# Main.net
KiCad netlist of a schematic drawn in Altium Designer
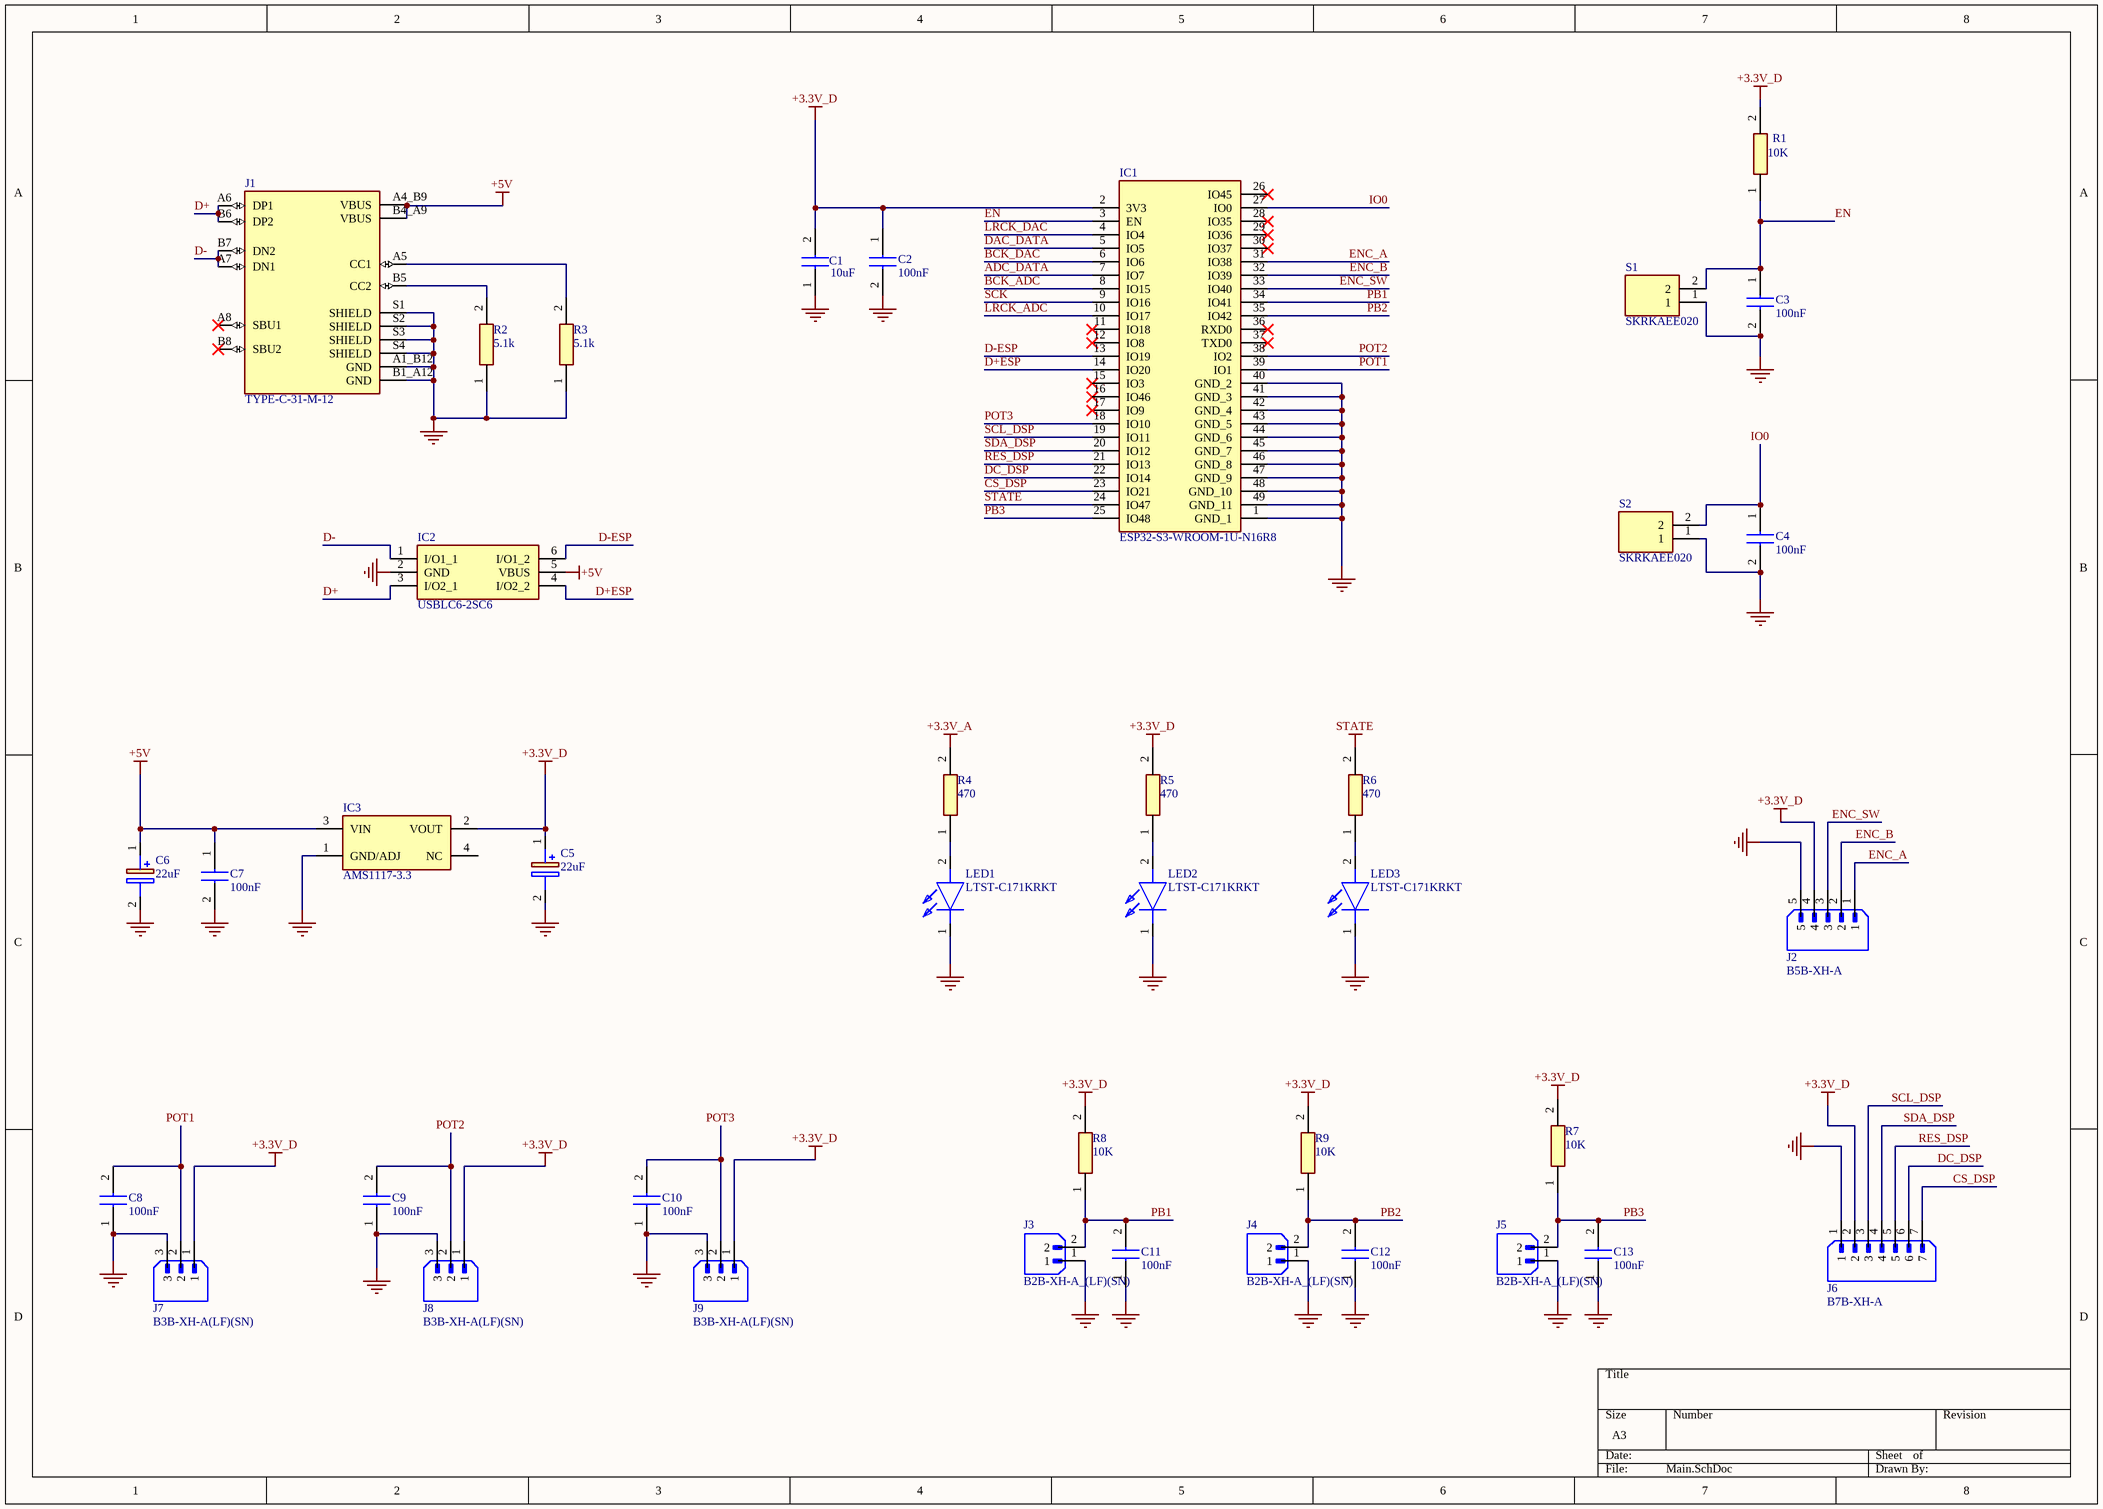
[diagram p0: Main.SchDoc]

(export (version "E")
  (design (tool "Eeschema 10.0.6"))
  (components
    (comp (ref "C1")
      (value "10uF")
      (footprint "SamacSys:CAPC3216X180N")
      (description "Capacitor")
      (fields
        (field (name "MANUFACTURER_PART_NUMBER") "CL31A106KAHNNNE")
        (field (name "MOUSER PART NUMBER") "187-CL31A106KAHNNNE")
      )
      (libsource (lib "SamacSys") (part "CL31A106KAHNNNE"))
    )
    (comp (ref "C2")
      (value "100nF")
      (footprint "SamacSys:CAPC1608X90N")
      (description "Capacitor")
      (fields
        (field (name "MANUFACTURER_PART_NUMBER") "CL10B104KC8NNNC")
        (field (name "MOUSER PART NUMBER") "187-CL10B104KC8NNNC")
      )
      (libsource (lib "SamacSys") (part "CL10B104KC8NNNC"))
    )
    (comp (ref "C3")
      (value "100nF")
      (footprint "SamacSys:CAPC1608X90N")
      (description "Capacitor")
      (fields
        (field (name "MANUFACTURER_PART_NUMBER") "CL10B104KC8NNNC")
        (field (name "MOUSER PART NUMBER") "187-CL10B104KC8NNNC")
      )
      (libsource (lib "SamacSys") (part "CL10B104KC8NNNC"))
    )
    (comp (ref "C4")
      (value "100nF")
      (footprint "SamacSys:CAPC1608X90N")
      (description "Capacitor")
      (fields
        (field (name "MANUFACTURER_PART_NUMBER") "CL10B104KC8NNNC")
        (field (name "MOUSER PART NUMBER") "187-CL10B104KC8NNNC")
      )
      (libsource (lib "SamacSys") (part "CL10B104KC8NNNC"))
    )
    (comp (ref "C5")
      (value "22uF")
      (footprint "SamacSys:CAPAE430X590N")
      (description "Capacitor Polarised")
      (fields (field (name "MANUFACTURER_PART_NUMBER") "RVT1C220M0405"))
      (libsource (lib "*") (part "RVT1C220M0405"))
    )
    (comp (ref "C6")
      (value "22uF")
      (footprint "SamacSys:CAPAE430X590N")
      (description "Capacitor Polarised")
      (fields (field (name "MANUFACTURER_PART_NUMBER") "RVT1C220M0405"))
      (libsource (lib "*") (part "RVT1C220M0405"))
    )
    (comp (ref "C7")
      (value "100nF")
      (footprint "SamacSys:CAPC1608X90N")
      (description "Capacitor")
      (fields
        (field (name "MANUFACTURER_PART_NUMBER") "CL10B104KC8NNNC")
        (field (name "MOUSER PART NUMBER") "187-CL10B104KC8NNNC")
      )
      (libsource (lib "SamacSys") (part "CL10B104KC8NNNC"))
    )
    (comp (ref "C8")
      (value "100nF")
      (footprint "SamacSys:CAPC1608X90N")
      (description "Capacitor")
      (fields
        (field (name "MANUFACTURER_PART_NUMBER") "CL10B104KC8NNNC")
        (field (name "MOUSER PART NUMBER") "187-CL10B104KC8NNNC")
      )
      (libsource (lib "SamacSys") (part "CL10B104KC8NNNC"))
    )
    (comp (ref "C9")
      (value "100nF")
      (footprint "SamacSys:CAPC1608X90N")
      (description "Capacitor")
      (fields
        (field (name "MANUFACTURER_PART_NUMBER") "CL10B104KC8NNNC")
        (field (name "MOUSER PART NUMBER") "187-CL10B104KC8NNNC")
      )
      (libsource (lib "SamacSys") (part "CL10B104KC8NNNC"))
    )
    (comp (ref "C10")
      (value "100nF")
      (footprint "SamacSys:CAPC1608X90N")
      (description "Capacitor")
      (fields
        (field (name "MANUFACTURER_PART_NUMBER") "CL10B104KC8NNNC")
        (field (name "MOUSER PART NUMBER") "187-CL10B104KC8NNNC")
      )
      (libsource (lib "SamacSys") (part "CL10B104KC8NNNC"))
    )
    (comp (ref "C11")
      (value "100nF")
      (footprint "SamacSys:CAPC1608X90N")
      (description "Capacitor")
      (fields
        (field (name "MANUFACTURER_PART_NUMBER") "CL10B104KC8NNNC")
        (field (name "MOUSER PART NUMBER") "187-CL10B104KC8NNNC")
      )
      (libsource (lib "SamacSys") (part "CL10B104KC8NNNC"))
    )
    (comp (ref "C12")
      (value "100nF")
      (footprint "SamacSys:CAPC1608X90N")
      (description "Capacitor")
      (fields
        (field (name "MANUFACTURER_PART_NUMBER") "CL10B104KC8NNNC")
        (field (name "MOUSER PART NUMBER") "187-CL10B104KC8NNNC")
      )
      (libsource (lib "SamacSys") (part "CL10B104KC8NNNC"))
    )
    (comp (ref "C13")
      (value "100nF")
      (footprint "SamacSys:CAPC1608X90N")
      (description "Capacitor")
      (fields
        (field (name "MANUFACTURER_PART_NUMBER") "CL10B104KC8NNNC")
        (field (name "MOUSER PART NUMBER") "187-CL10B104KC8NNNC")
      )
      (libsource (lib "SamacSys") (part "CL10B104KC8NNNC"))
    )
    (comp (ref "IC1")
      (value "ESP32-S3-WROOM-1U-N16R8")
      (footprint "SamacSys:ESP32S3WROOM1UN16R8")
      (description "Integrated Circuit")
      (fields (field (name "MOUSER PART NUMBER") "356-ESP32S3WM1UN16R8"))
      (libsource (lib "*") (part "ESP32-S3-WROOM-1U-N16R8"))
    )
    (comp (ref "IC2")
      (value "USBLC6-2SC6")
      (footprint "SamacSys:SOT95P280X145-6N")
      (description "Integrated Circuit")
      (fields (field (name "MOUSER PART NUMBER") "511-USBLC6-2SC6"))
      (libsource (lib "SamacSys") (part "USBLC6-2SC6"))
    )
    (comp (ref "IC3")
      (value "AMS1117-3.3")
      (footprint "SamacSys:SOT229P700X180-4N")
      (description "Integrated Circuit")
      (libsource (lib "*") (part "AMS1117-3.3"))
    )
    (comp (ref "J1")
      (value "TYPE-C-31-M-12")
      (footprint "HRO_TYPE-C-31-M-12")
      (description "USB Connectors 24 Receptacle 1 8.94*7.3mm RoHS")
      (fields (field (name "MF") "HRO Electronics Co., Ltd."))
      (libsource (lib "TYPE-C-31-M-12") (part "TYPE-C-31-M-12"))
    )
    (comp (ref "J2")
      (value "B5B-XH-A")
      (footprint "JST_B5B-XH-A")
      (description "Connector Header Through Hole 5 position 0.098 (2.50mm)")
      (fields (field (name "MF") "JST Sales"))
      (libsource (lib "B5B-XH-A") (part "B5B-XH-A"))
    )
    (comp (ref "J3")
      (value "B2B-XH-A_(LF)(SN)")
      (footprint "JST_B2B-XH-A_(LF)(SN)")
      (description "Connector Header Through Hole 2 position 0.098 (2.50mm)")
      (fields (field (name "MF") "JST Sales") (field (name "MP") "B2B-XH-A (LF)(SN)"))
      (libsource (lib "B2B-XH-A__LF__SN_") (part "B2B-XH-A_(LF)(SN)"))
    )
    (comp (ref "J4")
      (value "B2B-XH-A_(LF)(SN)")
      (footprint "JST_B2B-XH-A_(LF)(SN)")
      (description "Connector Header Through Hole 2 position 0.098 (2.50mm)")
      (fields (field (name "MF") "JST Sales") (field (name "MP") "B2B-XH-A (LF)(SN)"))
      (libsource (lib "B2B-XH-A__LF__SN_") (part "B2B-XH-A_(LF)(SN)"))
    )
    (comp (ref "J5")
      (value "B2B-XH-A_(LF)(SN)")
      (footprint "JST_B2B-XH-A_(LF)(SN)")
      (description "Connector Header Through Hole 2 position 0.098 (2.50mm)")
      (fields (field (name "MF") "JST Sales") (field (name "MP") "B2B-XH-A (LF)(SN)"))
      (libsource (lib "B2B-XH-A__LF__SN_") (part "B2B-XH-A_(LF)(SN)"))
    )
    (comp (ref "J6")
      (value "B7B-XH-A")
      (footprint "JST_B7B-XH-A")
      (description "Connector Header Through Hole 7 position 0.098 (2.50mm)")
      (fields (field (name "MF") "JST Sales"))
      (libsource (lib "B7B-XH-A") (part "B7B-XH-A"))
    )
    (comp (ref "J7")
      (value "B3B-XH-A(LF)(SN)")
      (footprint "JST_B3B-XH-A(LF)(SN)")
      (description "Connector Header Through Hole 3 position 0.098 (2.50mm)")
      (fields (field (name "MF") "JST Sales"))
      (libsource (lib "B3B-XH-A_LF__SN_") (part "B3B-XH-A(LF)(SN)"))
    )
    (comp (ref "J8")
      (value "B3B-XH-A(LF)(SN)")
      (footprint "JST_B3B-XH-A(LF)(SN)")
      (description "Connector Header Through Hole 3 position 0.098 (2.50mm)")
      (fields (field (name "MF") "JST Sales"))
      (libsource (lib "B3B-XH-A_LF__SN_") (part "B3B-XH-A(LF)(SN)"))
    )
    (comp (ref "J9")
      (value "B3B-XH-A(LF)(SN)")
      (footprint "JST_B3B-XH-A(LF)(SN)")
      (description "Connector Header Through Hole 3 position 0.098 (2.50mm)")
      (fields (field (name "MF") "JST Sales"))
      (libsource (lib "B3B-XH-A_LF__SN_") (part "B3B-XH-A(LF)(SN)"))
    )
    (comp (ref "LED1")
      (value "LTST-C171KRKT")
      (footprint "SamacSys:LEDM2012X90N")
      (description "LED")
      (fields (field (name "MOUSER PART NUMBER") "859-LTST-C171KRKT"))
      (libsource (lib "*") (part "LTST-C171KRKT"))
    )
    (comp (ref "LED2")
      (value "LTST-C171KRKT")
      (footprint "SamacSys:LEDM2012X90N")
      (description "LED")
      (fields (field (name "MOUSER PART NUMBER") "859-LTST-C171KRKT"))
      (libsource (lib "*") (part "LTST-C171KRKT"))
    )
    (comp (ref "LED3")
      (value "LTST-C171KRKT")
      (footprint "SamacSys:LEDM2012X90N")
      (description "LED")
      (fields (field (name "MOUSER PART NUMBER") "859-LTST-C171KRKT"))
      (libsource (lib "*") (part "LTST-C171KRKT"))
    )
    (comp (ref "R1")
      (value "10K")
      (footprint "SamacSys:RESC2012X60N")
      (description "Resistor")
      (fields
        (field (name "MANUFACTURER_PART_NUMBER") "AC0805JR-0710KL")
        (field (name "MOUSER PART NUMBER") "603-AC0805JR-0710KL")
      )
      (libsource (lib "SamacSys") (part "AC0805JR-0710KL"))
    )
    (comp (ref "R2")
      (value "5.1k")
      (footprint "SamacSys:ERA6AEB101V")
      (description "Resistor")
      (fields
        (field (name "MANUFACTURER_PART_NUMBER") "ERA-6AED512V")
        (field (name "MOUSER PART NUMBER") "667-ERA-6AED512V")
      )
      (libsource (lib "*") (part "ERA-6AED512V"))
    )
    (comp (ref "R3")
      (value "5.1k")
      (footprint "SamacSys:ERA6AEB101V")
      (description "Resistor")
      (fields
        (field (name "MANUFACTURER_PART_NUMBER") "ERA-6AED512V")
        (field (name "MOUSER PART NUMBER") "667-ERA-6AED512V")
      )
      (libsource (lib "*") (part "ERA-6AED512V"))
    )
    (comp (ref "R4")
      (value "470")
      (footprint "SamacSys:ERA3AEB101V")
      (description "Resistor")
      (fields
        (field (name "MANUFACTURER_PART_NUMBER") "ERA-3AEB471V")
        (field (name "MOUSER PART NUMBER") "667-ERA-3AEB471V")
      )
      (libsource (lib "*") (part "ERA-3AEB471V"))
    )
    (comp (ref "R5")
      (value "470")
      (footprint "SamacSys:ERA3AEB101V")
      (description "Resistor")
      (fields
        (field (name "MANUFACTURER_PART_NUMBER") "ERA-3AEB471V")
        (field (name "MOUSER PART NUMBER") "667-ERA-3AEB471V")
      )
      (libsource (lib "*") (part "ERA-3AEB471V"))
    )
    (comp (ref "R6")
      (value "470")
      (footprint "SamacSys:ERA3AEB101V")
      (description "Resistor")
      (fields
        (field (name "MANUFACTURER_PART_NUMBER") "ERA-3AEB471V")
        (field (name "MOUSER PART NUMBER") "667-ERA-3AEB471V")
      )
      (libsource (lib "*") (part "ERA-3AEB471V"))
    )
    (comp (ref "R7")
      (value "10K")
      (footprint "SamacSys:RESC2012X60N")
      (description "Resistor")
      (fields
        (field (name "MANUFACTURER_PART_NUMBER") "AC0805JR-0710KL")
        (field (name "MOUSER PART NUMBER") "603-AC0805JR-0710KL")
      )
      (libsource (lib "SamacSys") (part "AC0805JR-0710KL"))
    )
    (comp (ref "R8")
      (value "10K")
      (footprint "SamacSys:RESC2012X60N")
      (description "Resistor")
      (fields
        (field (name "MANUFACTURER_PART_NUMBER") "AC0805JR-0710KL")
        (field (name "MOUSER PART NUMBER") "603-AC0805JR-0710KL")
      )
      (libsource (lib "SamacSys") (part "AC0805JR-0710KL"))
    )
    (comp (ref "R9")
      (value "10K")
      (footprint "SamacSys:RESC2012X60N")
      (description "Resistor")
      (fields
        (field (name "MANUFACTURER_PART_NUMBER") "AC0805JR-0710KL")
        (field (name "MOUSER PART NUMBER") "603-AC0805JR-0710KL")
      )
      (libsource (lib "SamacSys") (part "AC0805JR-0710KL"))
    )
    (comp (ref "S1")
      (value "SKRKAEE020")
      (footprint "SamacSys:SKRKAEE020")
      (description "Switch")
      (fields (field (name "MOUSER PART NUMBER") "688-SKRKAEE020"))
      (libsource (lib "*") (part "SKRKAEE020"))
    )
    (comp (ref "S2")
      (value "SKRKAEE020")
      (footprint "SamacSys:SKRKAEE020")
      (description "Switch")
      (fields (field (name "MOUSER PART NUMBER") "688-SKRKAEE020"))
      (libsource (lib "*") (part "SKRKAEE020"))
    )
  )
  (nets
    (net (code "1") (name "+3.3V_A") (class "Default")
      (node (ref "R4") (pin "2") (pinfunction "2_2") (pintype "passive"))
    )
    (net (code "2") (name "+3.3V_D") (class "Default")
      (node (ref "C1") (pin "2") (pinfunction "2_2") (pintype "passive"))
      (node (ref "C2") (pin "1") (pinfunction "1_1") (pintype "passive"))
      (node (ref "C5") (pin "1") (pinfunction "+_1") (pintype "passive"))
      (node (ref "IC1") (pin "2") (pinfunction "3V3_2") (pintype "passive"))
      (node (ref "IC3") (pin "2") (pinfunction "VOUT_2") (pintype "passive"))
      (node (ref "J2") (pin "4") (pinfunction "4_4") (pintype "passive"))
      (node (ref "J6") (pin "2") (pinfunction "2_2") (pintype "passive"))
      (node (ref "J7") (pin "1") (pinfunction "1_1") (pintype "passive"))
      (node (ref "J8") (pin "1") (pinfunction "1_1") (pintype "passive"))
      (node (ref "J9") (pin "1") (pinfunction "1_1") (pintype "passive"))
      (node (ref "R1") (pin "2") (pinfunction "2_2") (pintype "passive"))
      (node (ref "R5") (pin "2") (pinfunction "2_2") (pintype "passive"))
      (node (ref "R7") (pin "2") (pinfunction "2_2") (pintype "passive"))
      (node (ref "R8") (pin "2") (pinfunction "2_2") (pintype "passive"))
      (node (ref "R9") (pin "2") (pinfunction "2_2") (pintype "passive"))
    )
    (net (code "3") (name "+5V") (class "Default")
      (node (ref "C6") (pin "1") (pinfunction "+_1") (pintype "passive"))
      (node (ref "C7") (pin "1") (pinfunction "1_1") (pintype "passive"))
      (node (ref "IC2") (pin "5") (pinfunction "VBUS_5") (pintype "passive"))
      (node (ref "IC3") (pin "3") (pinfunction "VIN_3") (pintype "passive"))
      (node (ref "J1") (pin "A4_B9") (pinfunction "VBUS_A4_B9") (pintype "power_in"))
      (node (ref "J1") (pin "B4_A9") (pinfunction "VBUS_B4_A9") (pintype "power_in"))
    )
    (net (code "4") (name "/ADC_DATA") (class "Default")
      (node (ref "IC1") (pin "7") (pinfunction "IO7_7") (pintype "passive"))
    )
    (net (code "5") (name "/BCK_ADC") (class "Default")
      (node (ref "IC1") (pin "8") (pinfunction "IO15_8") (pintype "passive"))
    )
    (net (code "6") (name "/BCK_DAC") (class "Default")
      (node (ref "IC1") (pin "6") (pinfunction "IO6_6") (pintype "passive"))
    )
    (net (code "7") (name "/CS_DSP") (class "Default")
      (node (ref "IC1") (pin "23") (pinfunction "IO21_23") (pintype "passive"))
      (node (ref "J6") (pin "7") (pinfunction "7_7") (pintype "passive"))
    )
    (net (code "8") (name "/D+") (class "Default")
      (node (ref "IC2") (pin "3") (pinfunction "I/O2_1_3") (pintype "passive"))
      (node (ref "J1") (pin "A6") (pinfunction "DP1_A6") (pintype "bidirectional"))
      (node (ref "J1") (pin "B6") (pinfunction "DP2_B6") (pintype "bidirectional"))
    )
    (net (code "9") (name "/D+ESP") (class "Default")
      (node (ref "IC1") (pin "14") (pinfunction "IO20_14") (pintype "passive"))
      (node (ref "IC2") (pin "4") (pinfunction "I/O2_2_4") (pintype "passive"))
    )
    (net (code "10") (name "/D-") (class "Default")
      (node (ref "IC2") (pin "1") (pinfunction "I/O1_1_1") (pintype "passive"))
      (node (ref "J1") (pin "A7") (pinfunction "DN1_A7") (pintype "bidirectional"))
      (node (ref "J1") (pin "B7") (pinfunction "DN2_B7") (pintype "bidirectional"))
    )
    (net (code "11") (name "/D-ESP") (class "Default")
      (node (ref "IC1") (pin "13") (pinfunction "IO19_13") (pintype "passive"))
      (node (ref "IC2") (pin "6") (pinfunction "I/O1_2_6") (pintype "passive"))
    )
    (net (code "12") (name "/DAC_DATA") (class "Default")
      (node (ref "IC1") (pin "5") (pinfunction "IO5_5") (pintype "passive"))
    )
    (net (code "13") (name "/DC_DSP") (class "Default")
      (node (ref "IC1") (pin "22") (pinfunction "IO14_22") (pintype "passive"))
      (node (ref "J6") (pin "6") (pinfunction "6_6") (pintype "passive"))
    )
    (net (code "14") (name "/EN") (class "Default")
      (node (ref "C3") (pin "1") (pinfunction "1_1") (pintype "passive"))
      (node (ref "IC1") (pin "3") (pinfunction "EN_3") (pintype "passive"))
      (node (ref "R1") (pin "1") (pinfunction "1_1") (pintype "passive"))
      (node (ref "S1") (pin "2") (pinfunction "2_2") (pintype "passive"))
    )
    (net (code "15") (name "/ENC_A") (class "Default")
      (node (ref "IC1") (pin "31") (pinfunction "IO38_31") (pintype "passive"))
      (node (ref "J2") (pin "1") (pinfunction "1_1") (pintype "passive"))
    )
    (net (code "16") (name "/ENC_B") (class "Default")
      (node (ref "IC1") (pin "32") (pinfunction "IO39_32") (pintype "passive"))
      (node (ref "J2") (pin "2") (pinfunction "2_2") (pintype "passive"))
    )
    (net (code "17") (name "/ENC_SW") (class "Default")
      (node (ref "IC1") (pin "33") (pinfunction "IO40_33") (pintype "passive"))
      (node (ref "J2") (pin "3") (pinfunction "3_3") (pintype "passive"))
    )
    (net (code "18") (name "/IO0") (class "Default")
      (node (ref "C4") (pin "1") (pinfunction "1_1") (pintype "passive"))
      (node (ref "IC1") (pin "27") (pinfunction "IO0_27") (pintype "passive"))
      (node (ref "S2") (pin "2") (pinfunction "2_2") (pintype "passive"))
    )
    (net (code "19") (name "/LRCK_ADC") (class "Default")
      (node (ref "IC1") (pin "10") (pinfunction "IO17_10") (pintype "passive"))
    )
    (net (code "20") (name "/LRCK_DAC") (class "Default")
      (node (ref "IC1") (pin "4") (pinfunction "IO4_4") (pintype "passive"))
    )
    (net (code "21") (name "/PB1") (class "Default")
      (node (ref "C11") (pin "2") (pinfunction "2_2") (pintype "passive"))
      (node (ref "IC1") (pin "34") (pinfunction "IO41_34") (pintype "passive"))
      (node (ref "J3") (pin "2") (pinfunction "2_2") (pintype "passive"))
      (node (ref "R8") (pin "1") (pinfunction "1_1") (pintype "passive"))
    )
    (net (code "22") (name "/PB2") (class "Default")
      (node (ref "C12") (pin "2") (pinfunction "2_2") (pintype "passive"))
      (node (ref "IC1") (pin "35") (pinfunction "IO42_35") (pintype "passive"))
      (node (ref "J4") (pin "2") (pinfunction "2_2") (pintype "passive"))
      (node (ref "R9") (pin "1") (pinfunction "1_1") (pintype "passive"))
    )
    (net (code "23") (name "/PB3") (class "Default")
      (node (ref "C13") (pin "2") (pinfunction "2_2") (pintype "passive"))
      (node (ref "IC1") (pin "25") (pinfunction "IO48_25") (pintype "passive"))
      (node (ref "J5") (pin "2") (pinfunction "2_2") (pintype "passive"))
      (node (ref "R7") (pin "1") (pinfunction "1_1") (pintype "passive"))
    )
    (net (code "24") (name "/POT1") (class "Default")
      (node (ref "C8") (pin "2") (pinfunction "2_2") (pintype "passive"))
      (node (ref "IC1") (pin "39") (pinfunction "IO1_39") (pintype "passive"))
      (node (ref "J7") (pin "2") (pinfunction "2_2") (pintype "passive"))
    )
    (net (code "25") (name "/POT2") (class "Default")
      (node (ref "C9") (pin "2") (pinfunction "2_2") (pintype "passive"))
      (node (ref "IC1") (pin "38") (pinfunction "IO2_38") (pintype "passive"))
      (node (ref "J8") (pin "2") (pinfunction "2_2") (pintype "passive"))
    )
    (net (code "26") (name "/POT3") (class "Default")
      (node (ref "C10") (pin "2") (pinfunction "2_2") (pintype "passive"))
      (node (ref "IC1") (pin "18") (pinfunction "IO10_18") (pintype "passive"))
      (node (ref "J9") (pin "2") (pinfunction "2_2") (pintype "passive"))
    )
    (net (code "27") (name "/RES_DSP") (class "Default")
      (node (ref "IC1") (pin "21") (pinfunction "IO13_21") (pintype "passive"))
      (node (ref "J6") (pin "5") (pinfunction "5_5") (pintype "passive"))
    )
    (net (code "28") (name "/SCK") (class "Default")
      (node (ref "IC1") (pin "9") (pinfunction "IO16_9") (pintype "passive"))
    )
    (net (code "29") (name "/SCL_DSP") (class "Default")
      (node (ref "IC1") (pin "19") (pinfunction "IO11_19") (pintype "passive"))
      (node (ref "J6") (pin "3") (pinfunction "3_3") (pintype "passive"))
    )
    (net (code "30") (name "/SDA_DSP") (class "Default")
      (node (ref "IC1") (pin "20") (pinfunction "IO12_20") (pintype "passive"))
      (node (ref "J6") (pin "4") (pinfunction "4_4") (pintype "passive"))
    )
    (net (code "31") (name "GND") (class "Default")
      (node (ref "C1") (pin "1") (pinfunction "1_1") (pintype "passive"))
      (node (ref "C10") (pin "1") (pinfunction "1_1") (pintype "passive"))
      (node (ref "C11") (pin "1") (pinfunction "1_1") (pintype "passive"))
      (node (ref "C12") (pin "1") (pinfunction "1_1") (pintype "passive"))
      (node (ref "C13") (pin "1") (pinfunction "1_1") (pintype "passive"))
      (node (ref "C2") (pin "2") (pinfunction "2_2") (pintype "passive"))
      (node (ref "C3") (pin "2") (pinfunction "2_2") (pintype "passive"))
      (node (ref "C4") (pin "2") (pinfunction "2_2") (pintype "passive"))
      (node (ref "C5") (pin "2") (pinfunction "-_2") (pintype "passive"))
      (node (ref "C6") (pin "2") (pinfunction "-_2") (pintype "passive"))
      (node (ref "C7") (pin "2") (pinfunction "2_2") (pintype "passive"))
      (node (ref "C8") (pin "1") (pinfunction "1_1") (pintype "passive"))
      (node (ref "C9") (pin "1") (pinfunction "1_1") (pintype "passive"))
      (node (ref "IC1") (pin "1") (pinfunction "GND_1_1") (pintype "passive"))
      (node (ref "IC1") (pin "40") (pinfunction "GND_2_40") (pintype "passive"))
      (node (ref "IC1") (pin "41") (pinfunction "GND_3_41") (pintype "passive"))
      (node (ref "IC1") (pin "42") (pinfunction "GND_4_42") (pintype "passive"))
      (node (ref "IC1") (pin "43") (pinfunction "GND_5_43") (pintype "passive"))
      (node (ref "IC1") (pin "44") (pinfunction "GND_6_44") (pintype "passive"))
      (node (ref "IC1") (pin "45") (pinfunction "GND_7_45") (pintype "passive"))
      (node (ref "IC1") (pin "46") (pinfunction "GND_8_46") (pintype "passive"))
      (node (ref "IC1") (pin "47") (pinfunction "GND_9_47") (pintype "passive"))
      (node (ref "IC1") (pin "48") (pinfunction "GND_10_48") (pintype "passive"))
      (node (ref "IC1") (pin "49") (pinfunction "GND_11_49") (pintype "passive"))
      (node (ref "IC2") (pin "2") (pinfunction "GND_2") (pintype "passive"))
      (node (ref "IC3") (pin "1") (pinfunction "GND/ADJ_1") (pintype "passive"))
      (node (ref "J1") (pin "A1_B12") (pinfunction "GND_A1_B12") (pintype "power_in"))
      (node (ref "J1") (pin "B1_A12") (pinfunction "GND_B1_A12") (pintype "power_in"))
      (node (ref "J1") (pin "S1") (pinfunction "SHIELD_S1") (pintype "passive"))
      (node (ref "J1") (pin "S2") (pinfunction "SHIELD_S2") (pintype "passive"))
      (node (ref "J1") (pin "S3") (pinfunction "SHIELD_S3") (pintype "passive"))
      (node (ref "J1") (pin "S4") (pinfunction "SHIELD_S4") (pintype "passive"))
      (node (ref "J2") (pin "5") (pinfunction "5_5") (pintype "passive"))
      (node (ref "J3") (pin "1") (pinfunction "1_1") (pintype "passive"))
      (node (ref "J4") (pin "1") (pinfunction "1_1") (pintype "passive"))
      (node (ref "J5") (pin "1") (pinfunction "1_1") (pintype "passive"))
      (node (ref "J6") (pin "1") (pinfunction "1_1") (pintype "passive"))
      (node (ref "J7") (pin "3") (pinfunction "3_3") (pintype "passive"))
      (node (ref "J8") (pin "3") (pinfunction "3_3") (pintype "passive"))
      (node (ref "J9") (pin "3") (pinfunction "3_3") (pintype "passive"))
      (node (ref "LED1") (pin "1") (pinfunction "K_1") (pintype "passive"))
      (node (ref "LED2") (pin "1") (pinfunction "K_1") (pintype "passive"))
      (node (ref "LED3") (pin "1") (pinfunction "K_1") (pintype "passive"))
      (node (ref "R2") (pin "1") (pinfunction "1_1") (pintype "passive"))
      (node (ref "R3") (pin "1") (pinfunction "1_1") (pintype "passive"))
      (node (ref "S1") (pin "1") (pinfunction "1_1") (pintype "passive"))
      (node (ref "S2") (pin "1") (pinfunction "1_1") (pintype "passive"))
    )
    (net (code "32") (name "Net-(J1-CC1)") (class "Default")
      (node (ref "J1") (pin "A5") (pinfunction "CC1_A5") (pintype "bidirectional"))
      (node (ref "R3") (pin "2") (pinfunction "2_2") (pintype "passive"))
    )
    (net (code "33") (name "Net-(J1-CC2)") (class "Default")
      (node (ref "J1") (pin "B5") (pinfunction "CC2_B5") (pintype "bidirectional"))
      (node (ref "R2") (pin "2") (pinfunction "2_2") (pintype "passive"))
    )
    (net (code "34") (name "Net-(LED1-A)") (class "Default")
      (node (ref "LED1") (pin "2") (pinfunction "A_2") (pintype "passive"))
      (node (ref "R4") (pin "1") (pinfunction "1_1") (pintype "passive"))
    )
    (net (code "35") (name "Net-(LED2-A)") (class "Default")
      (node (ref "LED2") (pin "2") (pinfunction "A_2") (pintype "passive"))
      (node (ref "R5") (pin "1") (pinfunction "1_1") (pintype "passive"))
    )
    (net (code "36") (name "Net-(LED3-A)") (class "Default")
      (node (ref "LED3") (pin "2") (pinfunction "A_2") (pintype "passive"))
      (node (ref "R6") (pin "1") (pinfunction "1_1") (pintype "passive"))
    )
    (net (code "37") (name "STATE") (class "Default")
      (node (ref "IC1") (pin "24") (pinfunction "IO47_24") (pintype "passive"))
      (node (ref "R6") (pin "2") (pinfunction "2_2") (pintype "passive"))
    )
    (net (code "38") (name "unconnected-(IC1-IO3-Pad15)") (class "Default")
      (node (ref "IC1") (pin "15") (pinfunction "IO3_15") (pintype "passive+no_connect"))
    )
    (net (code "39") (name "unconnected-(IC1-IO8-Pad12)") (class "Default")
      (node (ref "IC1") (pin "12") (pinfunction "IO8_12") (pintype "passive+no_connect"))
    )
    (net (code "40") (name "unconnected-(IC1-IO9-Pad17)") (class "Default")
      (node (ref "IC1") (pin "17") (pinfunction "IO9_17") (pintype "passive+no_connect"))
    )
    (net (code "41") (name "unconnected-(IC1-IO18-Pad11)") (class "Default")
      (node (ref "IC1") (pin "11") (pinfunction "IO18_11") (pintype "passive+no_connect"))
    )
    (net (code "42") (name "unconnected-(IC1-IO35-Pad28)") (class "Default")
      (node (ref "IC1") (pin "28") (pinfunction "IO35_28") (pintype "passive+no_connect"))
    )
    (net (code "43") (name "unconnected-(IC1-IO36-Pad29)") (class "Default")
      (node (ref "IC1") (pin "29") (pinfunction "IO36_29") (pintype "passive+no_connect"))
    )
    (net (code "44") (name "unconnected-(IC1-IO37-Pad30)") (class "Default")
      (node (ref "IC1") (pin "30") (pinfunction "IO37_30") (pintype "passive+no_connect"))
    )
    (net (code "45") (name "unconnected-(IC1-IO45-Pad26)") (class "Default")
      (node (ref "IC1") (pin "26") (pinfunction "IO45_26") (pintype "passive+no_connect"))
    )
    (net (code "46") (name "unconnected-(IC1-IO46-Pad16)") (class "Default")
      (node (ref "IC1") (pin "16") (pinfunction "IO46_16") (pintype "passive+no_connect"))
    )
    (net (code "47") (name "unconnected-(IC1-RXD0-Pad36)") (class "Default")
      (node (ref "IC1") (pin "36") (pinfunction "RXD0_36") (pintype "passive+no_connect"))
    )
    (net (code "48") (name "unconnected-(IC1-TXD0-Pad37)") (class "Default")
      (node (ref "IC1") (pin "37") (pinfunction "TXD0_37") (pintype "passive+no_connect"))
    )
    (net (code "49") (name "unconnected-(IC3-NC-Pad4)") (class "Default")
      (node (ref "IC3") (pin "4") (pinfunction "NC_4") (pintype "passive"))
    )
    (net (code "50") (name "unconnected-(J1-SBU1-PadA8)") (class "Default")
      (node (ref "J1") (pin "A8") (pinfunction "SBU1_A8") (pintype "bidirectional+no_connect"))
    )
    (net (code "51") (name "unconnected-(J1-SBU2-PadB8)") (class "Default")
      (node (ref "J1") (pin "B8") (pinfunction "SBU2_B8") (pintype "bidirectional+no_connect"))
    )
  )
)
